# Hephaestus.net
KiCad netlist of a schematic drawn in EAGLE
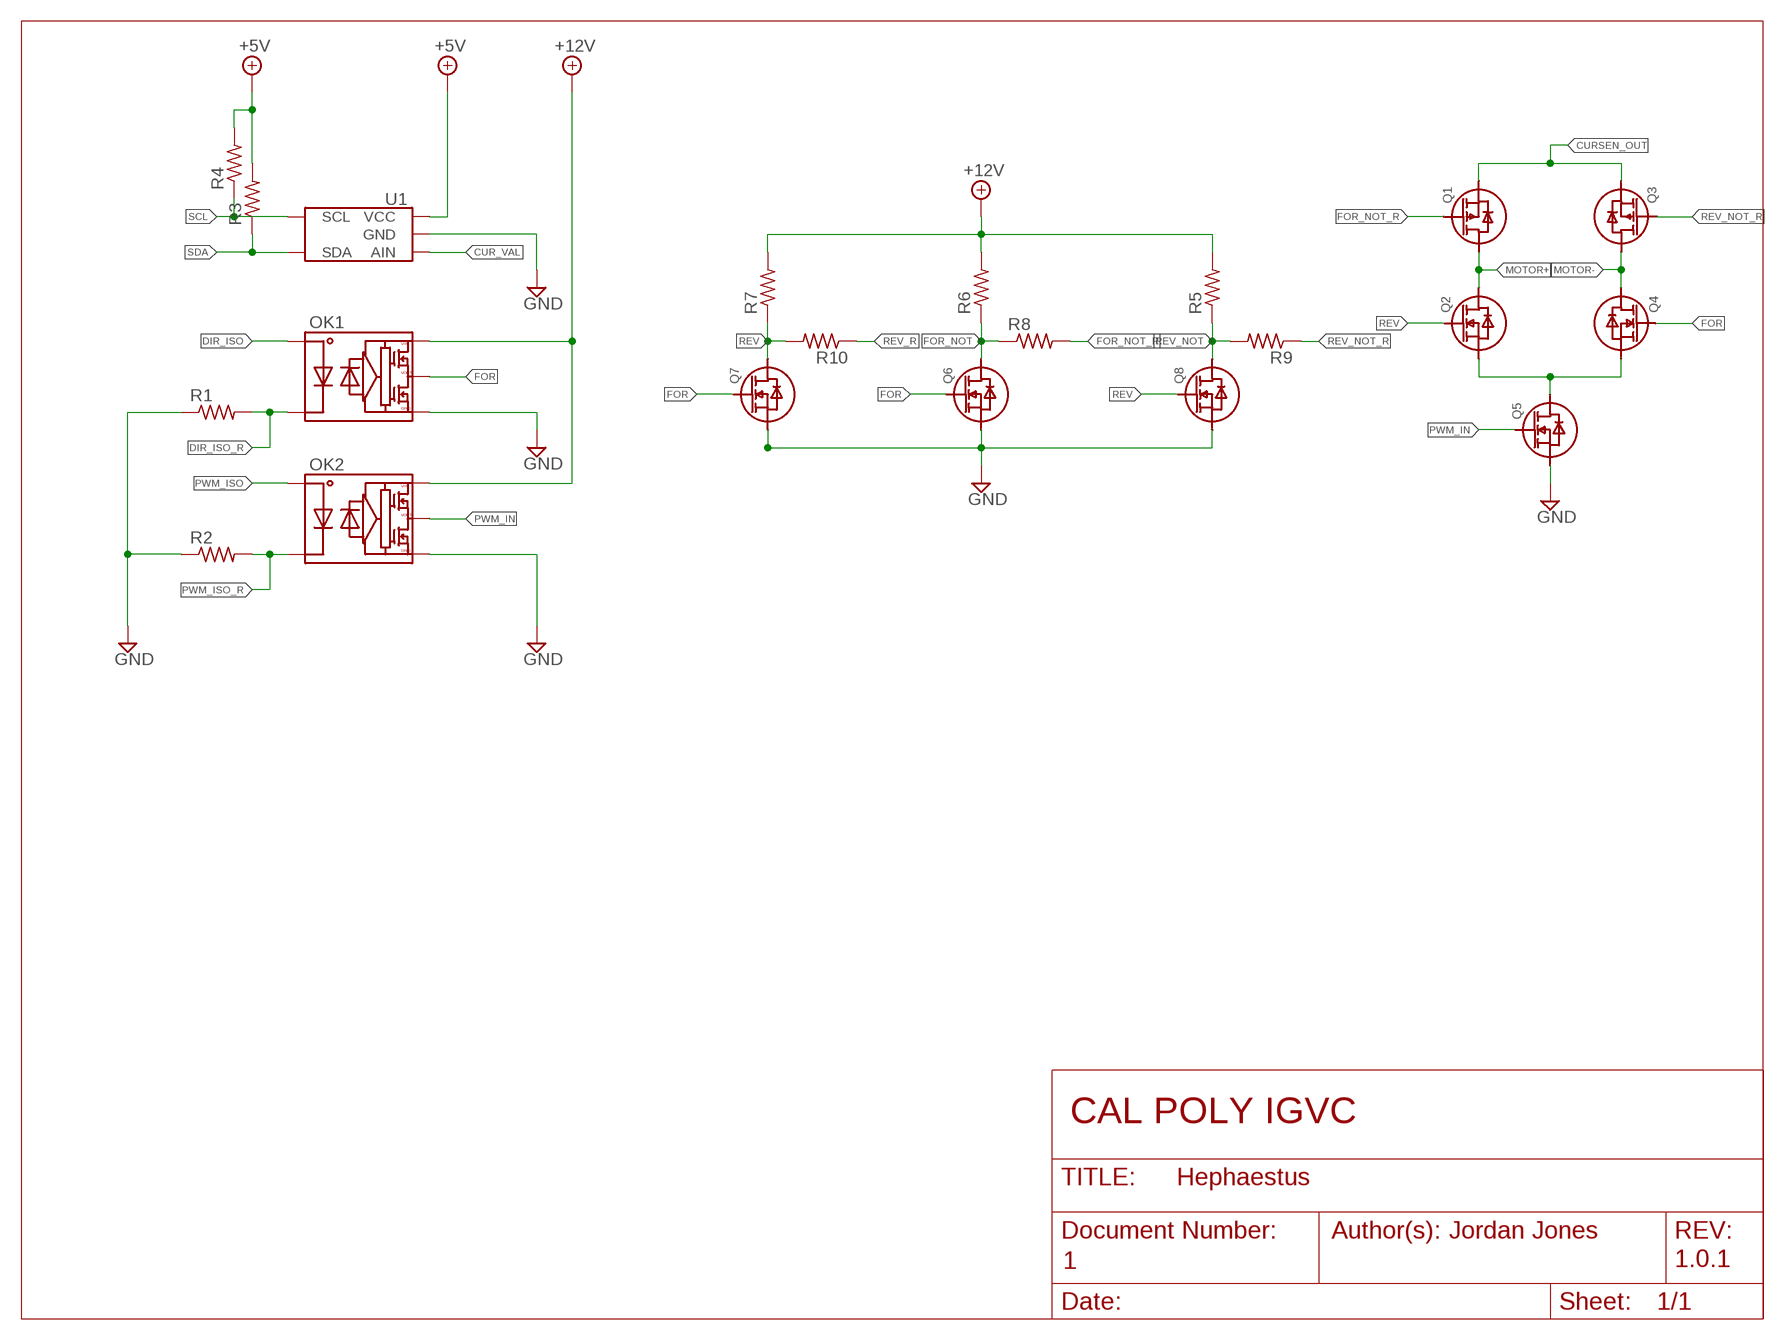
[diagram p0: schematic, sheet 1]

(export (version "E")
  (design (tool "Eeschema 10.0.6"))
  (components
    (comp (ref "OK1")
      (value "TLP152")
      (footprint "eagle-import:SOIC-6-5")
      (libsource (lib "eagle-import") (part "TLP152"))
    )
    (comp (ref "OK2")
      (value "TLP152")
      (footprint "eagle-import:SOIC-6-5")
      (libsource (lib "eagle-import") (part "TLP152"))
    )
    (comp (ref "Q1")
      (value "IPD50P04P413ATMA1")
      (footprint "eagle-import:TO-252-3")
      (libsource (lib "eagle-import") (part "IPD50P04P413ATMA1"))
    )
    (comp (ref "Q2")
      (value "IPD090N03L_G")
      (footprint "eagle-import:TO-252-3")
      (libsource (lib "eagle-import") (part "IPD090N03L_G"))
    )
    (comp (ref "Q3")
      (value "IPD50P04P413ATMA1")
      (footprint "eagle-import:TO-252-3")
      (libsource (lib "eagle-import") (part "IPD50P04P413ATMA1"))
    )
    (comp (ref "Q4")
      (value "IPD090N03L_G")
      (footprint "eagle-import:TO-252-3")
      (libsource (lib "eagle-import") (part "IPD090N03L_G"))
    )
    (comp (ref "Q5")
      (value "IPD090N03L_G")
      (footprint "eagle-import:TO-252-3")
      (libsource (lib "eagle-import") (part "IPD090N03L_G"))
    )
    (comp (ref "Q6")
      (value "DMN6140L-7")
      (footprint "eagle-import:SOT-23-3")
      (libsource (lib "eagle-import") (part "DMN6140L-7"))
    )
    (comp (ref "Q7")
      (value "DMN6140L-7")
      (footprint "eagle-import:SOT-23-3")
      (libsource (lib "eagle-import") (part "DMN6140L-7"))
    )
    (comp (ref "Q8")
      (value "DMN6140L-7")
      (footprint "eagle-import:SOT-23-3")
      (libsource (lib "eagle-import") (part "DMN6140L-7"))
    )
    (comp (ref "R1")
      (value "R-US_R0603")
      (footprint "eagle-import:R0603")
      (libsource (lib "eagle-import") (part "R-US_R0603"))
    )
    (comp (ref "R2")
      (value "R-US_R0603")
      (footprint "eagle-import:R0603")
      (libsource (lib "eagle-import") (part "R-US_R0603"))
    )
    (comp (ref "R3")
      (value "R-US_R0603")
      (footprint "eagle-import:R0603")
      (libsource (lib "eagle-import") (part "R-US_R0603"))
    )
    (comp (ref "R4")
      (value "R-US_R0603")
      (footprint "eagle-import:R0603")
      (libsource (lib "eagle-import") (part "R-US_R0603"))
    )
    (comp (ref "R5")
      (value "R-US_R0603")
      (footprint "eagle-import:R0603")
      (libsource (lib "eagle-import") (part "R-US_R0603"))
    )
    (comp (ref "R6")
      (value "R-US_R0603")
      (footprint "eagle-import:R0603")
      (libsource (lib "eagle-import") (part "R-US_R0603"))
    )
    (comp (ref "R7")
      (value "R-US_R0603")
      (footprint "eagle-import:R0603")
      (libsource (lib "eagle-import") (part "R-US_R0603"))
    )
    (comp (ref "R8")
      (value "R-US_R0603")
      (footprint "eagle-import:R0603")
      (libsource (lib "eagle-import") (part "R-US_R0603"))
    )
    (comp (ref "R9")
      (value "R-US_R0603")
      (footprint "eagle-import:R0603")
      (libsource (lib "eagle-import") (part "R-US_R0603"))
    )
    (comp (ref "R10")
      (value "R-US_R0603")
      (footprint "eagle-import:R0603")
      (libsource (lib "eagle-import") (part "R-US_R0603"))
    )
    (comp (ref "U1")
      (value "MCP3021A0T-E/OT")
      (footprint "eagle-import:SOT-23-5")
      (libsource (lib "eagle-import") (part "MCP3021A0T-E/OT"))
    )
  )
  (nets
    (net (code "1") (name "+5V") (class "Default")
      (node (ref "R3") (pin "2") (pinfunction "2_2") (pintype "passive"))
      (node (ref "R4") (pin "2") (pinfunction "2_2") (pintype "passive"))
      (node (ref "U1") (pin "P$1") (pinfunction "VCC_P$1") (pintype "bidirectional"))
    )
    (net (code "2") (name "+12V") (class "Default")
      (node (ref "OK1") (pin "P$6") (pinfunction "P$6_P$6") (pintype "bidirectional"))
      (node (ref "OK2") (pin "P$6") (pinfunction "P$6_P$6") (pintype "bidirectional"))
      (node (ref "R5") (pin "2") (pinfunction "2_2") (pintype "passive"))
      (node (ref "R6") (pin "2") (pinfunction "2_2") (pintype "passive"))
      (node (ref "R7") (pin "2") (pinfunction "2_2") (pintype "passive"))
    )
    (net (code "3") (name "CURSEN_OUT") (class "Default")
      (node (ref "Q1") (pin "P$2") (pinfunction "S_P$2") (pintype "bidirectional"))
      (node (ref "Q3") (pin "P$2") (pinfunction "S_P$2") (pintype "bidirectional"))
    )
    (net (code "4") (name "CUR_VAL") (class "Default")
      (node (ref "U1") (pin "P$3") (pinfunction "AIN_P$3") (pintype "bidirectional"))
    )
    (net (code "5") (name "DIR_ISO") (class "Default")
      (node (ref "OK1") (pin "P$1") (pinfunction "P$1_P$1") (pintype "bidirectional"))
    )
    (net (code "6") (name "DIR_ISO_R") (class "Default")
      (node (ref "OK1") (pin "P$3") (pinfunction "P$2_P$3") (pintype "bidirectional"))
      (node (ref "R1") (pin "2") (pinfunction "2_2") (pintype "passive"))
    )
    (net (code "7") (name "FOR") (class "Default")
      (node (ref "OK1") (pin "P$5") (pinfunction "P$5_P$5") (pintype "bidirectional"))
      (node (ref "Q4") (pin "P$1") (pinfunction "G_P$1") (pintype "bidirectional"))
      (node (ref "Q6") (pin "P$1") (pinfunction "G_P$1") (pintype "bidirectional"))
      (node (ref "Q7") (pin "P$1") (pinfunction "G_P$1") (pintype "bidirectional"))
    )
    (net (code "8") (name "FOR_NOT") (class "Default")
      (node (ref "Q6") (pin "P$3") (pinfunction "D_P$3") (pintype "bidirectional"))
      (node (ref "R6") (pin "1") (pinfunction "1_1") (pintype "passive"))
      (node (ref "R8") (pin "1") (pinfunction "1_1") (pintype "passive"))
    )
    (net (code "9") (name "FOR_NOT_R") (class "Default")
      (node (ref "Q1") (pin "P$1") (pinfunction "G_P$1") (pintype "bidirectional"))
      (node (ref "R8") (pin "2") (pinfunction "2_2") (pintype "passive"))
    )
    (net (code "10") (name "GND") (class "Default")
      (node (ref "OK1") (pin "P$4") (pinfunction "P$4_P$4") (pintype "bidirectional"))
      (node (ref "OK2") (pin "P$4") (pinfunction "P$4_P$4") (pintype "bidirectional"))
      (node (ref "Q5") (pin "P$2") (pinfunction "S_P$2") (pintype "bidirectional"))
      (node (ref "Q6") (pin "P$2") (pinfunction "S_P$2") (pintype "bidirectional"))
      (node (ref "Q7") (pin "P$2") (pinfunction "S_P$2") (pintype "bidirectional"))
      (node (ref "Q8") (pin "P$2") (pinfunction "S_P$2") (pintype "bidirectional"))
      (node (ref "R1") (pin "1") (pinfunction "1_1") (pintype "passive"))
      (node (ref "R2") (pin "1") (pinfunction "1_1") (pintype "passive"))
      (node (ref "U1") (pin "P$2") (pinfunction "GND_P$2") (pintype "bidirectional"))
    )
    (net (code "11") (name "MOTOR+") (class "Default")
      (node (ref "Q1") (pin "P$3") (pinfunction "D_P$3") (pintype "bidirectional"))
      (node (ref "Q2") (pin "P$3") (pinfunction "D_P$3") (pintype "bidirectional"))
    )
    (net (code "12") (name "MOTOR-") (class "Default")
      (node (ref "Q3") (pin "P$3") (pinfunction "D_P$3") (pintype "bidirectional"))
      (node (ref "Q4") (pin "P$3") (pinfunction "D_P$3") (pintype "bidirectional"))
    )
    (net (code "13") (name "Net-(Q2-S)") (class "Default")
      (node (ref "Q2") (pin "P$2") (pinfunction "S_P$2") (pintype "bidirectional"))
      (node (ref "Q4") (pin "P$2") (pinfunction "S_P$2") (pintype "bidirectional"))
      (node (ref "Q5") (pin "P$3") (pinfunction "D_P$3") (pintype "bidirectional"))
    )
    (net (code "14") (name "PWM_IN") (class "Default")
      (node (ref "OK2") (pin "P$5") (pinfunction "P$5_P$5") (pintype "bidirectional"))
      (node (ref "Q5") (pin "P$1") (pinfunction "G_P$1") (pintype "bidirectional"))
    )
    (net (code "15") (name "PWM_ISO") (class "Default")
      (node (ref "OK2") (pin "P$1") (pinfunction "P$1_P$1") (pintype "bidirectional"))
    )
    (net (code "16") (name "PWM_ISO_R") (class "Default")
      (node (ref "OK2") (pin "P$3") (pinfunction "P$2_P$3") (pintype "bidirectional"))
      (node (ref "R2") (pin "2") (pinfunction "2_2") (pintype "passive"))
    )
    (net (code "17") (name "REV") (class "Default")
      (node (ref "Q2") (pin "P$1") (pinfunction "G_P$1") (pintype "bidirectional"))
      (node (ref "Q7") (pin "P$3") (pinfunction "D_P$3") (pintype "bidirectional"))
      (node (ref "Q8") (pin "P$1") (pinfunction "G_P$1") (pintype "bidirectional"))
      (node (ref "R10") (pin "2") (pinfunction "2_2") (pintype "passive"))
      (node (ref "R7") (pin "1") (pinfunction "1_1") (pintype "passive"))
    )
    (net (code "18") (name "REV_NOT") (class "Default")
      (node (ref "Q8") (pin "P$3") (pinfunction "D_P$3") (pintype "bidirectional"))
      (node (ref "R5") (pin "1") (pinfunction "1_1") (pintype "passive"))
      (node (ref "R9") (pin "2") (pinfunction "2_2") (pintype "passive"))
    )
    (net (code "19") (name "REV_NOT_R") (class "Default")
      (node (ref "Q3") (pin "P$1") (pinfunction "G_P$1") (pintype "bidirectional"))
      (node (ref "R9") (pin "1") (pinfunction "1_1") (pintype "passive"))
    )
    (net (code "20") (name "REV_R") (class "Default")
      (node (ref "R10") (pin "1") (pinfunction "1_1") (pintype "passive"))
    )
    (net (code "21") (name "SCL") (class "Default")
      (node (ref "R4") (pin "1") (pinfunction "1_1") (pintype "passive"))
      (node (ref "U1") (pin "P$6") (pinfunction "SCL_P$6") (pintype "bidirectional"))
    )
    (net (code "22") (name "SDA") (class "Default")
      (node (ref "R3") (pin "1") (pinfunction "1_1") (pintype "passive"))
      (node (ref "U1") (pin "P$4") (pinfunction "SDA_P$4") (pintype "bidirectional"))
    )
  )
)
